# PeripheralConnector.net
KiCad netlist of a schematic drawn in Altium Designer
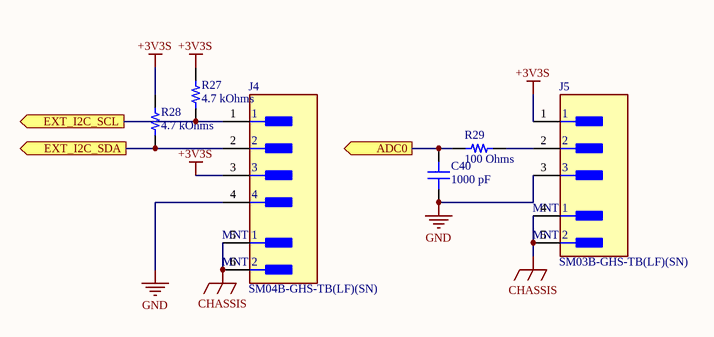
[diagram p0: PeripheralConnector.SchDoc]

(export (version "E")
  (design (tool "Eeschema 10.0.6"))
  (components
    (comp (ref "C40")
      (value "1000 pF")
      (footprint "CAP 0402_1005")
      (description "CAP CER 1000PF 50V C0G/NP0 0402")
      (fields
        (field (name "PART NUMBER") "UMK105CG102JVHF")
        (field (name "CAPACITANCE") "1000 pF")
        (field (name "MANUFACTURER") "Taiyo Yuden")
      )
      (libsource (lib "Celestial Altium Library - altium_library") (part "Capacitor"))
    )
    (comp (ref "J4")
      (value "SM04B-GHS-TB(LF)(SN)")
      (footprint "FP-SM04B-GHS-TB_LF_SN-MFG")
      (description "CONN HEADER SMD R/A 4POS 1.25MM")
      (libsource (lib "Altium Content Vault") (part "f4320a1371cd6270e33bce1916c33c0"))
    )
    (comp (ref "J5")
      (value "SM03B-GHS-TB(LF)(SN)")
      (footprint "FP-SM03B-GHS-TB_LF_SN-MFG")
      (description "CONN HEADER SMD R/A 3POS 1.25MM")
      (libsource (lib "Altium Content Vault") (part "13850a6865a90496d8e6d51657cef87"))
    )
    (comp (ref "R27")
      (value "4.7 kOhms")
      (footprint "RES 0402_1005")
      (description "RES 4.7K OHM 1% 1/16W 0402")
      (fields
        (field (name "PART NUMBER") "WR04X4701FTL")
        (field (name "MANUFACTURER") "Walsin Technology Corporation")
      )
      (libsource (lib "Celestial Altium Library - altium_library") (part "Resistor"))
    )
    (comp (ref "R28")
      (value "4.7 kOhms")
      (footprint "RES 0402_1005")
      (description "RES 4.7K OHM 1% 1/16W 0402")
      (fields
        (field (name "PART NUMBER") "WR04X4701FTL")
        (field (name "MANUFACTURER") "Walsin Technology Corporation")
      )
      (libsource (lib "Celestial Altium Library - altium_library") (part "Resistor"))
    )
    (comp (ref "R29")
      (value "100 Ohms")
      (footprint "RES 0402_1005")
      (description "RES 100 OHM 1% 1/16W 0402")
      (fields
        (field (name "PART NUMBER") "WR04X1000FTL")
        (field (name "MANUFACTURER") "Walsin Technology Corporation")
      )
      (libsource (lib "Celestial Altium Library - altium_library") (part "Resistor"))
    )
  )
  (nets
    (net (code "1") (name "+3V3S") (class "Default")
      (node (ref "J4") (pin "3") (pinfunction "3_3") (pintype "passive"))
      (node (ref "J5") (pin "1") (pinfunction "1_1") (pintype "passive"))
      (node (ref "R27") (pin "2") (pinfunction "2_2") (pintype "passive"))
      (node (ref "R28") (pin "2") (pinfunction "2_2") (pintype "passive"))
    )
    (net (code "2") (name "/ADC0") (class "Default")
      (node (ref "C40") (pin "2") (pinfunction "2_2") (pintype "passive"))
      (node (ref "R29") (pin "1") (pinfunction "1_1") (pintype "passive"))
    )
    (net (code "3") (name "/EXT_I2C_SCL") (class "Default")
      (node (ref "J4") (pin "1") (pinfunction "1_1") (pintype "passive"))
      (node (ref "R27") (pin "1") (pinfunction "1_1") (pintype "passive"))
    )
    (net (code "4") (name "/EXT_I2C_SDA") (class "Default")
      (node (ref "J4") (pin "2") (pinfunction "2_2") (pintype "passive"))
      (node (ref "R28") (pin "1") (pinfunction "1_1") (pintype "passive"))
    )
    (net (code "5") (name "CHASSIS") (class "Default")
      (node (ref "J4") (pin "5") (pinfunction "MNT_1_5") (pintype "passive"))
      (node (ref "J4") (pin "6") (pinfunction "MNT_2_6") (pintype "passive"))
      (node (ref "J5") (pin "4") (pinfunction "MNT_1_4") (pintype "passive"))
      (node (ref "J5") (pin "5") (pinfunction "MNT_2_5") (pintype "passive"))
    )
    (net (code "6") (name "GND") (class "Default")
      (node (ref "C40") (pin "1") (pinfunction "1_1") (pintype "passive"))
      (node (ref "J4") (pin "4") (pinfunction "4_4") (pintype "passive"))
      (node (ref "J5") (pin "3") (pinfunction "3_3") (pintype "passive"))
    )
    (net (code "7") (name "Net-(J5-Pad2)") (class "Default")
      (node (ref "J5") (pin "2") (pinfunction "2_2") (pintype "passive"))
      (node (ref "R29") (pin "2") (pinfunction "2_2") (pintype "passive"))
    )
  )
)
